# hdmi_to_8pin_header_vstimp.net
KiCad netlist of a schematic drawn in Altium Designer
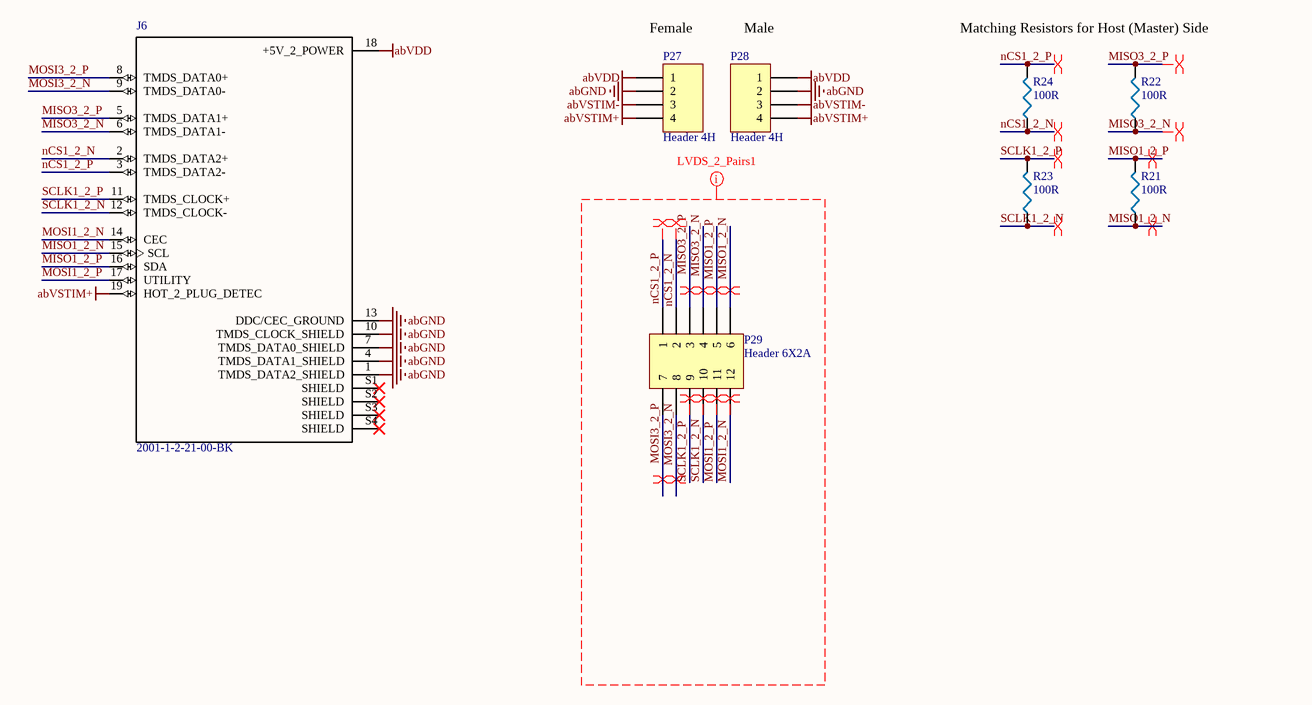
[diagram p0: hdmi_to_8pin_header_vstimp.SchDoc]

(export (version "E")
  (design (tool "Eeschema 10.0.6"))
  (components
    (comp (ref "J6")
      (value "2001-1-2-21-00-BK")
      (footprint "*CNC_2001-1-2-21-00-BK_2001-1-2-21-00-BK(Primary)")
      (description "Mini Hdmi 19p Female Smt")
      (fields (field (name "DIGI-KEY_PART_NUMBER") "1175-1704-1-ND") (field (name "MANUFACTURER") "CNC Tech"))
      (libsource (lib "cnc_hdmi") (part "2001-1-2-21-00-BK"))
    )
    (comp (ref "P27")
      (value "Header 4H")
      (footprint "sullins_conn_headers:PPTC041LGBN-RC")
      (description "Header, 4-Pin, Right Angle")
      (fields
        (field (name "MANUFACTURER") "Sullins Connector Solutions")
        (field (name "MANUFACTURER PART NUMBER") "PPTC041LGBN-RC")
        (field (name "PUBLISHER") "Altium Limited")
      )
      (libsource (lib "") (part "Header 4H_1"))
    )
    (comp (ref "P28")
      (value "Header 4H")
      (footprint "sullins_conn_headers:PEC04SBAN")
      (description "Header, 4-Pin, Right Angle")
      (fields
        (field (name "MANUFACTURER") "Sullins Connector Solutions")
        (field (name "MANUFACTURER PART NUMBER") "PEC04SBAN")
        (field (name "PUBLISHER") "Altium Limited")
      )
      (libsource (lib "Miscellaneous Connectors") (part "Header 4H"))
    )
    (comp (ref "P29")
      (value "Header 6X2A")
      (footprint "sullins_conn_headers:PPPC062LJBN-RC")
      (description "Header, 6-Pin, Dual row")
      (fields
        (field (name "MANUFACTURER") "Sullins Connector Solutions")
        (field (name "MANUFACTURER PART NUMBER") "PPPC062LJBN-RC")
        (field (name "PUBLISHER") "Altium Limited")
      )
      (libsource (lib "Miscellaneous Connectors") (part "Header 6X2A"))
    )
    (comp (ref "R21")
      (value "100R")
      (footprint "standard_components:R0805")
      (description "ERJ-6ENF1000V")
      (fields (field (name "MANUFACTURER") "Panasonic Electronic Components") (field (name "TOLERANCE") "1%"))
      (libsource (lib "standard_components") (part "RES100"))
    )
    (comp (ref "R22")
      (value "100R")
      (footprint "standard_components:R0805")
      (description "ERJ-6ENF1000V")
      (fields (field (name "MANUFACTURER") "Panasonic Electronic Components") (field (name "TOLERANCE") "1%"))
      (libsource (lib "standard_components") (part "RES100"))
    )
    (comp (ref "R23")
      (value "100R")
      (footprint "standard_components:R0805")
      (description "ERJ-6ENF1000V")
      (fields (field (name "MANUFACTURER") "Panasonic Electronic Components") (field (name "TOLERANCE") "1%"))
      (libsource (lib "standard_components") (part "RES100"))
    )
    (comp (ref "R24")
      (value "100R")
      (footprint "standard_components:R0805")
      (description "ERJ-6ENF1000V")
      (fields (field (name "MANUFACTURER") "Panasonic Electronic Components") (field (name "TOLERANCE") "1%"))
      (libsource (lib "standard_components") (part "RES100"))
    )
  )
  (nets
    (net (code "1") (name "/MISO1_2_N") (class "Default")
      (node (ref "J6") (pin "15") (pinfunction "SCL_15") (pintype "bidirectional"))
      (node (ref "P29") (pin "6") (pinfunction "6_6") (pintype "passive"))
      (node (ref "R21") (pin "1") (pinfunction "1_1") (pintype "passive"))
    )
    (net (code "2") (name "/MISO1_2_P") (class "Default")
      (node (ref "J6") (pin "16") (pinfunction "SDA_16") (pintype "bidirectional"))
      (node (ref "P29") (pin "5") (pinfunction "5_5") (pintype "passive"))
      (node (ref "R21") (pin "2") (pinfunction "2_2") (pintype "passive"))
    )
    (net (code "3") (name "/MISO3_2_N") (class "Default")
      (node (ref "J6") (pin "6") (pinfunction "TMDS_DATA1-_6") (pintype "bidirectional"))
      (node (ref "P29") (pin "4") (pinfunction "4_4") (pintype "passive"))
      (node (ref "R22") (pin "1") (pinfunction "1_1") (pintype "passive"))
    )
    (net (code "4") (name "/MISO3_2_P") (class "Default")
      (node (ref "J6") (pin "5") (pinfunction "TMDS_DATA1+_5") (pintype "bidirectional"))
      (node (ref "P29") (pin "3") (pinfunction "3_3") (pintype "passive"))
      (node (ref "R22") (pin "2") (pinfunction "2_2") (pintype "passive"))
    )
    (net (code "5") (name "/MOSI1_2_N") (class "Default")
      (node (ref "J6") (pin "14") (pinfunction "CEC_14") (pintype "bidirectional"))
      (node (ref "P29") (pin "12") (pinfunction "12_12") (pintype "passive"))
    )
    (net (code "6") (name "/MOSI1_2_P") (class "Default")
      (node (ref "J6") (pin "17") (pinfunction "UTILITY_17") (pintype "bidirectional"))
      (node (ref "P29") (pin "11") (pinfunction "11_11") (pintype "passive"))
    )
    (net (code "7") (name "/MOSI3_2_N") (class "Default")
      (node (ref "J6") (pin "9") (pinfunction "TMDS_DATA0-_9") (pintype "bidirectional"))
      (node (ref "P29") (pin "8") (pinfunction "8_8") (pintype "passive"))
    )
    (net (code "8") (name "/MOSI3_2_P") (class "Default")
      (node (ref "J6") (pin "8") (pinfunction "TMDS_DATA0+_8") (pintype "bidirectional"))
      (node (ref "P29") (pin "7") (pinfunction "7_7") (pintype "passive"))
    )
    (net (code "9") (name "/SCLK1_2_N") (class "Default")
      (node (ref "J6") (pin "12") (pinfunction "TMDS_CLOCK-_12") (pintype "bidirectional"))
      (node (ref "P29") (pin "10") (pinfunction "10_10") (pintype "passive"))
      (node (ref "R23") (pin "1") (pinfunction "1_1") (pintype "passive"))
    )
    (net (code "10") (name "/SCLK1_2_P") (class "Default")
      (node (ref "J6") (pin "11") (pinfunction "TMDS_CLOCK+_11") (pintype "bidirectional"))
      (node (ref "P29") (pin "9") (pinfunction "9_9") (pintype "passive"))
      (node (ref "R23") (pin "2") (pinfunction "2_2") (pintype "passive"))
    )
    (net (code "11") (name "/nCS1_2_N") (class "Default")
      (node (ref "J6") (pin "2") (pinfunction "TMDS_DATA2+_2") (pintype "bidirectional"))
      (node (ref "P29") (pin "2") (pinfunction "2_2") (pintype "passive"))
      (node (ref "R24") (pin "1") (pinfunction "1_1") (pintype "passive"))
    )
    (net (code "12") (name "/nCS1_2_P") (class "Default")
      (node (ref "J6") (pin "3") (pinfunction "TMDS_DATA2-_3") (pintype "bidirectional"))
      (node (ref "P29") (pin "1") (pinfunction "1_1") (pintype "passive"))
      (node (ref "R24") (pin "2") (pinfunction "2_2") (pintype "passive"))
    )
    (net (code "13") (name "abGND") (class "Default")
      (node (ref "J6") (pin "1") (pinfunction "TMDS_DATA2_SHIELD_1") (pintype "power_in"))
      (node (ref "J6") (pin "10") (pinfunction "TMDS_CLOCK_SHIELD_10") (pintype "power_in"))
      (node (ref "J6") (pin "13") (pinfunction "DDC/CEC_GROUND_13") (pintype "power_in"))
      (node (ref "J6") (pin "4") (pinfunction "TMDS_DATA1_SHIELD_4") (pintype "power_in"))
      (node (ref "J6") (pin "7") (pinfunction "TMDS_DATA0_SHIELD_7") (pintype "power_in"))
      (node (ref "P27") (pin "2") (pinfunction "2_2") (pintype "passive"))
      (node (ref "P28") (pin "2") (pinfunction "2_2") (pintype "passive"))
    )
    (net (code "14") (name "abVDD") (class "Default")
      (node (ref "J6") (pin "18") (pinfunction "+5V_2_POWER_18") (pintype "power_in"))
      (node (ref "P27") (pin "1") (pinfunction "1_1") (pintype "passive"))
      (node (ref "P28") (pin "1") (pinfunction "1_1") (pintype "passive"))
    )
    (net (code "15") (name "abVSTIM+") (class "Default")
      (node (ref "J6") (pin "19") (pinfunction "HOT_2_PLUG_DETEC_19") (pintype "bidirectional"))
      (node (ref "P27") (pin "4") (pinfunction "4_4") (pintype "passive"))
      (node (ref "P28") (pin "4") (pinfunction "4_4") (pintype "passive"))
    )
    (net (code "16") (name "abVSTIM-") (class "Default")
      (node (ref "P27") (pin "3") (pinfunction "3_3") (pintype "passive"))
      (node (ref "P28") (pin "3") (pinfunction "3_3") (pintype "passive"))
    )
    (net (code "17") (name "unconnected-(J6-SHIELD-PadS1)") (class "Default")
      (node (ref "J6") (pin "S1") (pinfunction "SHIELD_S1") (pintype "power_in+no_connect"))
    )
    (net (code "18") (name "unconnected-(J6-SHIELD-PadS2)") (class "Default")
      (node (ref "J6") (pin "S2") (pinfunction "SHIELD_S2") (pintype "power_in+no_connect"))
    )
    (net (code "19") (name "unconnected-(J6-SHIELD-PadS3)") (class "Default")
      (node (ref "J6") (pin "S3") (pinfunction "SHIELD_S3") (pintype "power_in+no_connect"))
    )
    (net (code "20") (name "unconnected-(J6-SHIELD-PadS4)") (class "Default")
      (node (ref "J6") (pin "S4") (pinfunction "SHIELD_S4") (pintype "power_in+no_connect"))
    )
  )
)
